# BatMeas5_2_JST.net
KiCad netlist of a schematic drawn in EAGLE
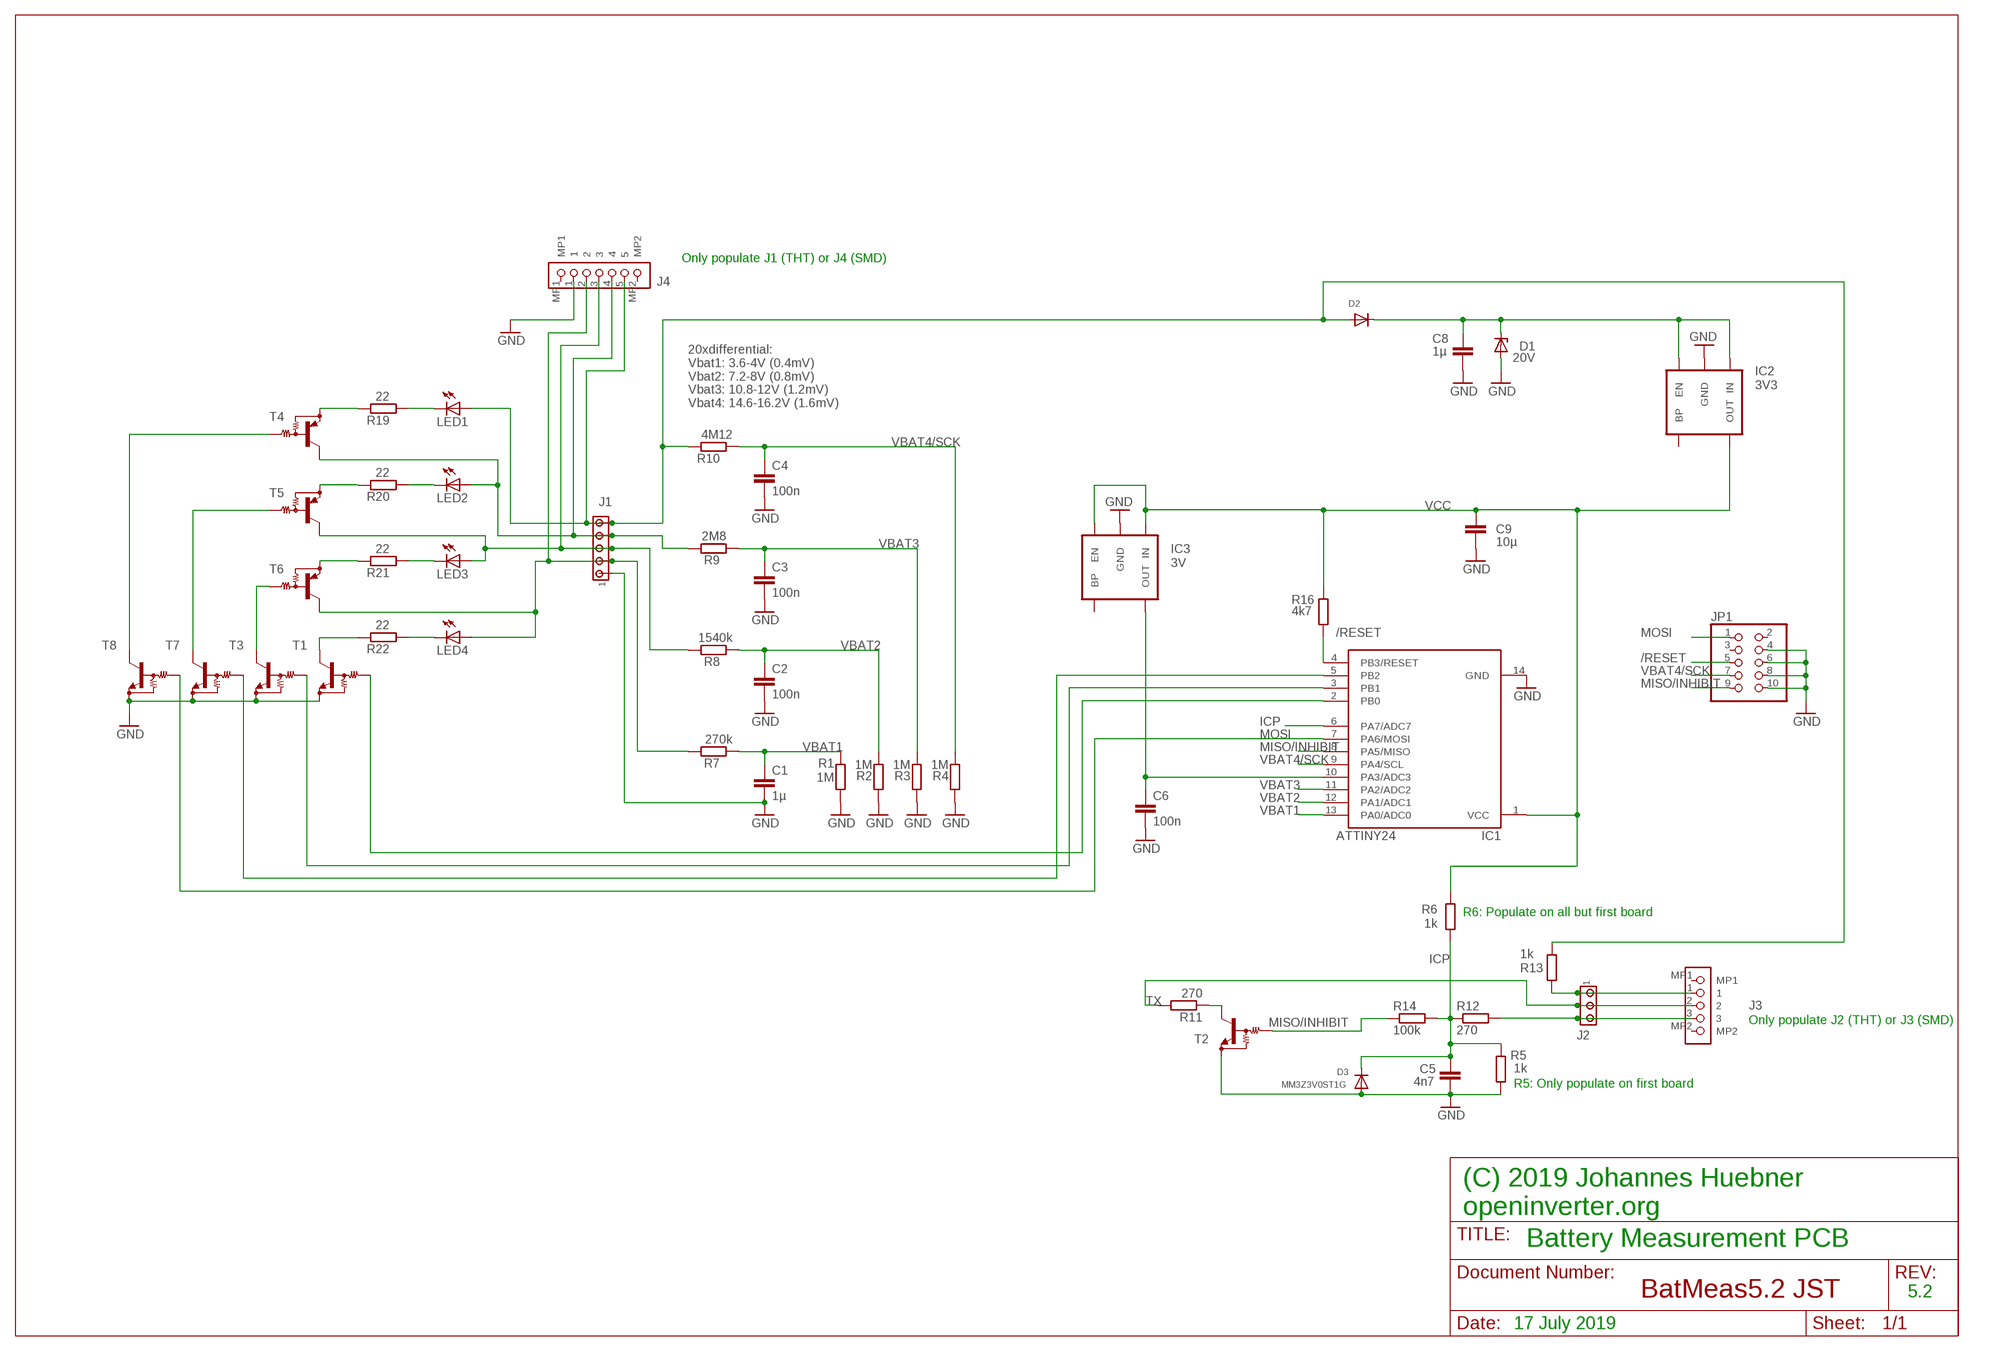
[diagram p0: schematic, sheet 1]

(export (version "E")
  (design (tool "Eeschema 10.0.6"))
  (components
    (comp (ref "C1")
      (value "1µ")
      (footprint "eagle-import:C0603")
      (libsource (lib "eagle-import") (part "C-EUC0603"))
    )
    (comp (ref "C2")
      (value "100n")
      (footprint "eagle-import:C0603")
      (libsource (lib "eagle-import") (part "C-EUC0603"))
    )
    (comp (ref "C3")
      (value "100n")
      (footprint "eagle-import:C0603")
      (libsource (lib "eagle-import") (part "C-EUC0603"))
    )
    (comp (ref "C4")
      (value "100n")
      (footprint "eagle-import:C0603")
      (libsource (lib "eagle-import") (part "C-EUC0603"))
    )
    (comp (ref "C5")
      (value "4n7")
      (footprint "eagle-import:C0603")
      (libsource (lib "eagle-import") (part "C-EUC0603"))
    )
    (comp (ref "C6")
      (value "100n")
      (footprint "eagle-import:C0603")
      (libsource (lib "eagle-import") (part "C-EUC0603"))
    )
    (comp (ref "C8")
      (value "1µ")
      (footprint "eagle-import:C0805")
      (libsource (lib "eagle-import") (part "C-EUC0805"))
    )
    (comp (ref "C9")
      (value "10µ")
      (footprint "eagle-import:C0805")
      (libsource (lib "eagle-import") (part "C-EUC0805"))
    )
    (comp (ref "D1")
      (value "20V")
      (footprint "eagle-import:SMB")
      (libsource (lib "eagle-import") (part "ZENER-DIODESMB"))
    )
    (comp (ref "D2")
      (value "DIODESOD-323F")
      (footprint "eagle-import:SOD-323F")
      (libsource (lib "eagle-import") (part "DIODESOD-323F"))
    )
    (comp (ref "D3")
      (value "MM3Z3V0ST1G")
      (footprint "eagle-import:SOD-323F")
      (libsource (lib "eagle-import") (part "DIODESOD-323F"))
    )
    (comp (ref "IC1")
      (value "ATTINY24")
      (footprint "eagle-import:SO014")
      (libsource (lib "eagle-import") (part "ATTINY24"))
    )
    (comp (ref "IC2")
      (value "3V3")
      (footprint "eagle-import:SOT23-5")
      (libsource (lib "eagle-import") (part "V_REG_LDOSMD"))
    )
    (comp (ref "IC3")
      (value "3V")
      (footprint "eagle-import:SOT23-5")
      (libsource (lib "eagle-import") (part "V_REG_LDOSMD"))
    )
    (comp (ref "J1")
      (value "MTA05-100")
      (footprint "eagle-import:10X05MTA")
      (libsource (lib "eagle-import") (part "MTA05-100"))
    )
    (comp (ref "J2")
      (value "MTA03-100")
      (footprint "eagle-import:10X03MTA")
      (libsource (lib "eagle-import") (part "MTA03-100"))
    )
    (comp (ref "J3")
      (value "BM03B-PASS-1-TFT_(LF)(SN)")
      (footprint "eagle-import:BM03BPASS1TFTLFSN")
      (fields (field (name "MANUFACTURER_PART_NUMBER") "BM03B-PASS-1-TFT (LF)(SN)"))
      (libsource (lib "eagle-import") (part "BM03B-PASS-1-TFT_(LF)(SN)"))
    )
    (comp (ref "J4")
      (value "BM05B-PASS-1-TFT_(LF)(SN)SMD")
      (footprint "eagle-import:BM05BPASS1TFTLFSN")
      (libsource (lib "eagle-import") (part "BM05B-PASS-1-TFT_(LF)(SN)SMD"))
    )
    (comp (ref "JP1")
      (value "PINHD-2X5")
      (footprint "eagle-import:2X05")
      (libsource (lib "eagle-import") (part "PINHD-2X5"))
    )
    (comp (ref "LED1")
      (value "150060GS75000")
      (footprint "eagle-import:CHIPLED_0805")
      (libsource (lib "eagle-import") (part "LEDCHIPLED_0805"))
    )
    (comp (ref "LED2")
      (value "150060GS75000")
      (footprint "eagle-import:CHIPLED_0805")
      (libsource (lib "eagle-import") (part "LEDCHIPLED_0805"))
    )
    (comp (ref "LED3")
      (value "150060GS75000")
      (footprint "eagle-import:CHIPLED_0805")
      (libsource (lib "eagle-import") (part "LEDCHIPLED_0805"))
    )
    (comp (ref "LED4")
      (value "150060GS75000")
      (footprint "eagle-import:CHIPLED_0805")
      (libsource (lib "eagle-import") (part "LEDCHIPLED_0805"))
    )
    (comp (ref "R1")
      (value "1M")
      (footprint "eagle-import:R0603")
      (libsource (lib "eagle-import") (part "R-EU_R0603"))
    )
    (comp (ref "R2")
      (value "1M")
      (footprint "eagle-import:R0603")
      (libsource (lib "eagle-import") (part "R-EU_R0603"))
    )
    (comp (ref "R3")
      (value "1M")
      (footprint "eagle-import:R0603")
      (libsource (lib "eagle-import") (part "R-EU_R0603"))
    )
    (comp (ref "R4")
      (value "1M")
      (footprint "eagle-import:R0603")
      (libsource (lib "eagle-import") (part "R-EU_R0603"))
    )
    (comp (ref "R5")
      (value "1k")
      (footprint "eagle-import:R0603")
      (libsource (lib "eagle-import") (part "R-EU_R0603"))
    )
    (comp (ref "R6")
      (value "1k")
      (footprint "eagle-import:R0603")
      (libsource (lib "eagle-import") (part "R-EU_R0603"))
    )
    (comp (ref "R7")
      (value "270k")
      (footprint "eagle-import:R0603")
      (libsource (lib "eagle-import") (part "R-EU_R0603"))
    )
    (comp (ref "R8")
      (value "1540k")
      (footprint "eagle-import:R0603")
      (libsource (lib "eagle-import") (part "R-EU_R0603"))
    )
    (comp (ref "R9")
      (value "2M8")
      (footprint "eagle-import:R0603")
      (libsource (lib "eagle-import") (part "R-EU_R0603"))
    )
    (comp (ref "R10")
      (value "4M12")
      (footprint "eagle-import:R0603")
      (libsource (lib "eagle-import") (part "R-EU_R0603"))
    )
    (comp (ref "R11")
      (value "270")
      (footprint "eagle-import:R0603")
      (libsource (lib "eagle-import") (part "R-EU_R0603"))
    )
    (comp (ref "R12")
      (value "270")
      (footprint "eagle-import:R0603")
      (libsource (lib "eagle-import") (part "R-EU_R0603"))
    )
    (comp (ref "R13")
      (value "1k")
      (footprint "eagle-import:R0603")
      (libsource (lib "eagle-import") (part "R-EU_R0603"))
    )
    (comp (ref "R14")
      (value "100k")
      (footprint "eagle-import:R0603")
      (libsource (lib "eagle-import") (part "R-EU_R0603"))
    )
    (comp (ref "R16")
      (value "4k7")
      (footprint "eagle-import:R0603")
      (libsource (lib "eagle-import") (part "R-EU_R0603"))
    )
    (comp (ref "R19")
      (value "22")
      (footprint "eagle-import:R0805")
      (libsource (lib "eagle-import") (part "R-EU_R0805"))
    )
    (comp (ref "R20")
      (value "22")
      (footprint "eagle-import:R0805")
      (libsource (lib "eagle-import") (part "R-EU_R0805"))
    )
    (comp (ref "R21")
      (value "22")
      (footprint "eagle-import:R0805")
      (libsource (lib "eagle-import") (part "R-EU_R0805"))
    )
    (comp (ref "R22")
      (value "22")
      (footprint "eagle-import:R0805")
      (libsource (lib "eagle-import") (part "R-EU_R0805"))
    )
    (comp (ref "T1")
      (value "MMUN2233")
      (footprint "eagle-import:SC59-BEC")
      (libsource (lib "eagle-import") (part "-NPN_DRIVER-SC59-BECMUN2211T1"))
    )
    (comp (ref "T2")
      (value "MMUN2233")
      (footprint "eagle-import:SC59-BEC")
      (libsource (lib "eagle-import") (part "-NPN_DRIVER-SC59-BECMUN2211T1"))
    )
    (comp (ref "T3")
      (value "MMUN2233")
      (footprint "eagle-import:SC59-BEC")
      (libsource (lib "eagle-import") (part "-NPN_DRIVER-SC59-BECMUN2211T1"))
    )
    (comp (ref "T4")
      (value "MMUN2111LT1G")
      (footprint "eagle-import:SC59-BEC")
      (libsource (lib "eagle-import") (part "-PNP_DRIVER-SC59-BECMUN2111T1"))
    )
    (comp (ref "T5")
      (value "MMUN2111LT1G")
      (footprint "eagle-import:SC59-BEC")
      (libsource (lib "eagle-import") (part "-PNP_DRIVER-SC59-BECMUN2111T1"))
    )
    (comp (ref "T6")
      (value "MMUN2111LT1G")
      (footprint "eagle-import:SC59-BEC")
      (libsource (lib "eagle-import") (part "-PNP_DRIVER-SC59-BECMUN2111T1"))
    )
    (comp (ref "T7")
      (value "MMUN2233")
      (footprint "eagle-import:SC59-BEC")
      (libsource (lib "eagle-import") (part "-NPN_DRIVER-SC59-BECMUN2211T1"))
    )
    (comp (ref "T8")
      (value "MMUN2233")
      (footprint "eagle-import:SC59-BEC")
      (libsource (lib "eagle-import") (part "-NPN_DRIVER-SC59-BECMUN2211T1"))
    )
  )
  (nets
    (net (code "1") (name "/ICP") (class "Default")
      (node (ref "C5") (pin "1") (pinfunction "1_1") (pintype "passive"))
      (node (ref "D3") (pin "C") (pinfunction "C_C") (pintype "passive"))
      (node (ref "IC1") (pin "6") (pinfunction "PA7/ADC7_6") (pintype "bidirectional"))
      (node (ref "R12") (pin "1") (pinfunction "1_1") (pintype "passive"))
      (node (ref "R14") (pin "2") (pinfunction "2_2") (pintype "passive"))
      (node (ref "R5") (pin "2") (pinfunction "2_2") (pintype "passive"))
      (node (ref "R6") (pin "1") (pinfunction "1_1") (pintype "passive"))
    )
    (net (code "2") (name "/MISO{slash}INHIBIT") (class "Default")
      (node (ref "IC1") (pin "8") (pinfunction "PA5/MISO_8") (pintype "bidirectional"))
      (node (ref "JP1") (pin "9") (pinfunction "9_9") (pintype "passive"))
      (node (ref "R14") (pin "1") (pinfunction "1_1") (pintype "passive"))
      (node (ref "T2") (pin "B") (pinfunction "B_B") (pintype "passive"))
    )
    (net (code "3") (name "/MOSI") (class "Default")
      (node (ref "IC1") (pin "7") (pinfunction "PA6/MOSI_7") (pintype "bidirectional"))
      (node (ref "JP1") (pin "1") (pinfunction "1_1") (pintype "passive"))
      (node (ref "T8") (pin "B") (pinfunction "B_B") (pintype "passive"))
    )
    (net (code "4") (name "/TX") (class "Default")
      (node (ref "J2") (pin "2") (pinfunction "2_2") (pintype "passive"))
      (node (ref "J3") (pin "2") (pinfunction "2_2") (pintype "bidirectional"))
      (node (ref "R11") (pin "2") (pinfunction "2_2") (pintype "passive"))
    )
    (net (code "5") (name "/VBAT1") (class "Default")
      (node (ref "C1") (pin "1") (pinfunction "1_1") (pintype "passive"))
      (node (ref "IC1") (pin "13") (pinfunction "PA0/ADC0_13") (pintype "bidirectional"))
      (node (ref "R1") (pin "1") (pinfunction "1_1") (pintype "passive"))
      (node (ref "R7") (pin "1") (pinfunction "1_1") (pintype "passive"))
    )
    (net (code "6") (name "/VBAT2") (class "Default")
      (node (ref "C2") (pin "1") (pinfunction "1_1") (pintype "passive"))
      (node (ref "IC1") (pin "12") (pinfunction "PA1/ADC1_12") (pintype "bidirectional"))
      (node (ref "R2") (pin "1") (pinfunction "1_1") (pintype "passive"))
      (node (ref "R8") (pin "1") (pinfunction "1_1") (pintype "passive"))
    )
    (net (code "7") (name "/VBAT3") (class "Default")
      (node (ref "C3") (pin "1") (pinfunction "1_1") (pintype "passive"))
      (node (ref "IC1") (pin "11") (pinfunction "PA2/ADC2_11") (pintype "bidirectional"))
      (node (ref "R3") (pin "1") (pinfunction "1_1") (pintype "passive"))
      (node (ref "R9") (pin "1") (pinfunction "1_1") (pintype "passive"))
    )
    (net (code "8") (name "/VBAT4{slash}SCK") (class "Default")
      (node (ref "C4") (pin "1") (pinfunction "1_1") (pintype "passive"))
      (node (ref "IC1") (pin "9") (pinfunction "PA4/SCL_9") (pintype "bidirectional"))
      (node (ref "JP1") (pin "7") (pinfunction "7_7") (pintype "passive"))
      (node (ref "R10") (pin "1") (pinfunction "1_1") (pintype "passive"))
      (node (ref "R4") (pin "1") (pinfunction "1_1") (pintype "passive"))
    )
    (net (code "9") (name "/VCC") (class "Default")
      (node (ref "C9") (pin "1") (pinfunction "1_1") (pintype "passive"))
      (node (ref "IC1") (pin "1") (pinfunction "VCC_1") (pintype "bidirectional"))
      (node (ref "IC2") (pin "5") (pinfunction "OUT_5") (pintype "passive"))
      (node (ref "IC3") (pin "1") (pinfunction "IN_1") (pintype "input"))
      (node (ref "IC3") (pin "3") (pinfunction "EN_3") (pintype "input"))
      (node (ref "R16") (pin "1") (pinfunction "1_1") (pintype "passive"))
      (node (ref "R6") (pin "2") (pinfunction "2_2") (pintype "passive"))
    )
    (net (code "10") (name "/{slash}RESET") (class "Default")
      (node (ref "IC1") (pin "4") (pinfunction "PB3/RESET_4") (pintype "bidirectional"))
      (node (ref "JP1") (pin "5") (pinfunction "5_5") (pintype "passive"))
      (node (ref "R16") (pin "2") (pinfunction "2_2") (pintype "passive"))
    )
    (net (code "11") (name "GND") (class "Default")
      (node (ref "C1") (pin "2") (pinfunction "2_2") (pintype "passive"))
      (node (ref "C2") (pin "2") (pinfunction "2_2") (pintype "passive"))
      (node (ref "C3") (pin "2") (pinfunction "2_2") (pintype "passive"))
      (node (ref "C4") (pin "2") (pinfunction "2_2") (pintype "passive"))
      (node (ref "C5") (pin "2") (pinfunction "2_2") (pintype "passive"))
      (node (ref "C6") (pin "2") (pinfunction "2_2") (pintype "passive"))
      (node (ref "C8") (pin "2") (pinfunction "2_2") (pintype "passive"))
      (node (ref "C9") (pin "2") (pinfunction "2_2") (pintype "passive"))
      (node (ref "D1") (pin "A") (pinfunction "A_A") (pintype "passive"))
      (node (ref "D3") (pin "A") (pinfunction "A_A") (pintype "passive"))
      (node (ref "IC1") (pin "14") (pinfunction "GND_14") (pintype "bidirectional"))
      (node (ref "IC2") (pin "2") (pinfunction "GND_2") (pintype "input"))
      (node (ref "IC3") (pin "2") (pinfunction "GND_2") (pintype "input"))
      (node (ref "J1") (pin "1") (pinfunction "1_1") (pintype "passive"))
      (node (ref "J4") (pin "1") (pinfunction "1_1") (pintype "bidirectional"))
      (node (ref "JP1") (pin "10") (pinfunction "10_10") (pintype "passive"))
      (node (ref "JP1") (pin "4") (pinfunction "4_4") (pintype "passive"))
      (node (ref "JP1") (pin "6") (pinfunction "6_6") (pintype "passive"))
      (node (ref "JP1") (pin "8") (pinfunction "8_8") (pintype "passive"))
      (node (ref "R1") (pin "2") (pinfunction "2_2") (pintype "passive"))
      (node (ref "R2") (pin "2") (pinfunction "2_2") (pintype "passive"))
      (node (ref "R3") (pin "2") (pinfunction "2_2") (pintype "passive"))
      (node (ref "R4") (pin "2") (pinfunction "2_2") (pintype "passive"))
      (node (ref "R5") (pin "1") (pinfunction "1_1") (pintype "passive"))
      (node (ref "T1") (pin "E") (pinfunction "E_E") (pintype "passive"))
      (node (ref "T2") (pin "E") (pinfunction "E_E") (pintype "passive"))
      (node (ref "T3") (pin "E") (pinfunction "E_E") (pintype "passive"))
      (node (ref "T7") (pin "E") (pinfunction "E_E") (pintype "passive"))
      (node (ref "T8") (pin "E") (pinfunction "E_E") (pintype "passive"))
    )
    (net (code "12") (name "Net-(D2-PadA)") (class "Default")
      (node (ref "D2") (pin "A") (pinfunction "A_A") (pintype "passive"))
      (node (ref "J1") (pin "5") (pinfunction "5_5") (pintype "passive"))
      (node (ref "J4") (pin "5") (pinfunction "5_5") (pintype "bidirectional"))
      (node (ref "LED1") (pin "A") (pinfunction "A_A") (pintype "passive"))
      (node (ref "R10") (pin "2") (pinfunction "2_2") (pintype "passive"))
      (node (ref "R13") (pin "1") (pinfunction "1_1") (pintype "passive"))
    )
    (net (code "13") (name "Net-(IC1-PA3{slash}ADC3)") (class "Default")
      (node (ref "C6") (pin "1") (pinfunction "1_1") (pintype "passive"))
      (node (ref "IC1") (pin "10") (pinfunction "PA3/ADC3_10") (pintype "bidirectional"))
      (node (ref "IC3") (pin "5") (pinfunction "OUT_5") (pintype "passive"))
    )
    (net (code "14") (name "Net-(IC1-PB0)") (class "Default")
      (node (ref "IC1") (pin "2") (pinfunction "PB0_2") (pintype "bidirectional"))
      (node (ref "T1") (pin "B") (pinfunction "B_B") (pintype "passive"))
    )
    (net (code "15") (name "Net-(IC1-PB1)") (class "Default")
      (node (ref "IC1") (pin "3") (pinfunction "PB1_3") (pintype "bidirectional"))
      (node (ref "T3") (pin "B") (pinfunction "B_B") (pintype "passive"))
    )
    (net (code "16") (name "Net-(IC1-PB2)") (class "Default")
      (node (ref "IC1") (pin "5") (pinfunction "PB2_5") (pintype "bidirectional"))
      (node (ref "T7") (pin "B") (pinfunction "B_B") (pintype "passive"))
    )
    (net (code "17") (name "Net-(IC2-EN)") (class "Default")
      (node (ref "C8") (pin "1") (pinfunction "1_1") (pintype "passive"))
      (node (ref "D1") (pin "C") (pinfunction "C_C") (pintype "passive"))
      (node (ref "D2") (pin "C") (pinfunction "C_C") (pintype "passive"))
      (node (ref "IC2") (pin "1") (pinfunction "IN_1") (pintype "input"))
      (node (ref "IC2") (pin "3") (pinfunction "EN_3") (pintype "input"))
    )
    (net (code "18") (name "Net-(J1-Pad2)") (class "Default")
      (node (ref "J1") (pin "2") (pinfunction "2_2") (pintype "passive"))
      (node (ref "J4") (pin "2") (pinfunction "2_2") (pintype "bidirectional"))
      (node (ref "LED4") (pin "A") (pinfunction "A_A") (pintype "passive"))
      (node (ref "R7") (pin "2") (pinfunction "2_2") (pintype "passive"))
      (node (ref "T6") (pin "C") (pinfunction "C_C") (pintype "passive"))
    )
    (net (code "19") (name "Net-(J1-Pad3)") (class "Default")
      (node (ref "J1") (pin "3") (pinfunction "3_3") (pintype "passive"))
      (node (ref "J4") (pin "3") (pinfunction "3_3") (pintype "bidirectional"))
      (node (ref "LED3") (pin "A") (pinfunction "A_A") (pintype "passive"))
      (node (ref "R8") (pin "2") (pinfunction "2_2") (pintype "passive"))
      (node (ref "T5") (pin "C") (pinfunction "C_C") (pintype "passive"))
    )
    (net (code "20") (name "Net-(J1-Pad4)") (class "Default")
      (node (ref "J1") (pin "4") (pinfunction "4_4") (pintype "passive"))
      (node (ref "J4") (pin "4") (pinfunction "4_4") (pintype "bidirectional"))
      (node (ref "LED2") (pin "A") (pinfunction "A_A") (pintype "passive"))
      (node (ref "R9") (pin "2") (pinfunction "2_2") (pintype "passive"))
      (node (ref "T4") (pin "C") (pinfunction "C_C") (pintype "passive"))
    )
    (net (code "21") (name "Net-(J2-Pad1)") (class "Default")
      (node (ref "J2") (pin "1") (pinfunction "1_1") (pintype "passive"))
      (node (ref "J3") (pin "1") (pinfunction "1_1") (pintype "bidirectional"))
      (node (ref "R13") (pin "2") (pinfunction "2_2") (pintype "passive"))
    )
    (net (code "22") (name "Net-(J2-Pad3)") (class "Default")
      (node (ref "J2") (pin "3") (pinfunction "3_3") (pintype "passive"))
      (node (ref "J3") (pin "3") (pinfunction "3_3") (pintype "bidirectional"))
      (node (ref "R12") (pin "2") (pinfunction "2_2") (pintype "passive"))
    )
    (net (code "23") (name "Net-(LED1-PadC)") (class "Default")
      (node (ref "LED1") (pin "C") (pinfunction "C_C") (pintype "passive"))
      (node (ref "R19") (pin "1") (pinfunction "1_1") (pintype "passive"))
    )
    (net (code "24") (name "Net-(LED2-PadC)") (class "Default")
      (node (ref "LED2") (pin "C") (pinfunction "C_C") (pintype "passive"))
      (node (ref "R20") (pin "1") (pinfunction "1_1") (pintype "passive"))
    )
    (net (code "25") (name "Net-(LED3-PadC)") (class "Default")
      (node (ref "LED3") (pin "C") (pinfunction "C_C") (pintype "passive"))
      (node (ref "R21") (pin "1") (pinfunction "1_1") (pintype "passive"))
    )
    (net (code "26") (name "Net-(LED4-PadC)") (class "Default")
      (node (ref "LED4") (pin "C") (pinfunction "C_C") (pintype "passive"))
      (node (ref "R22") (pin "1") (pinfunction "1_1") (pintype "passive"))
    )
    (net (code "27") (name "Net-(R11-Pad1)") (class "Default")
      (node (ref "R11") (pin "1") (pinfunction "1_1") (pintype "passive"))
      (node (ref "T2") (pin "C") (pinfunction "C_C") (pintype "passive"))
    )
    (net (code "28") (name "Net-(R19-Pad2)") (class "Default")
      (node (ref "R19") (pin "2") (pinfunction "2_2") (pintype "passive"))
      (node (ref "T4") (pin "E") (pinfunction "E_E") (pintype "passive"))
    )
    (net (code "29") (name "Net-(R20-Pad2)") (class "Default")
      (node (ref "R20") (pin "2") (pinfunction "2_2") (pintype "passive"))
      (node (ref "T5") (pin "E") (pinfunction "E_E") (pintype "passive"))
    )
    (net (code "30") (name "Net-(R21-Pad2)") (class "Default")
      (node (ref "R21") (pin "2") (pinfunction "2_2") (pintype "passive"))
      (node (ref "T6") (pin "E") (pinfunction "E_E") (pintype "passive"))
    )
    (net (code "31") (name "Net-(R22-Pad2)") (class "Default")
      (node (ref "R22") (pin "2") (pinfunction "2_2") (pintype "passive"))
      (node (ref "T1") (pin "C") (pinfunction "C_C") (pintype "passive"))
    )
    (net (code "32") (name "Net-(T3-PadC)") (class "Default")
      (node (ref "T3") (pin "C") (pinfunction "C_C") (pintype "passive"))
      (node (ref "T6") (pin "B") (pinfunction "B_B") (pintype "passive"))
    )
    (net (code "33") (name "Net-(T4-PadB)") (class "Default")
      (node (ref "T4") (pin "B") (pinfunction "B_B") (pintype "passive"))
      (node (ref "T8") (pin "C") (pinfunction "C_C") (pintype "passive"))
    )
    (net (code "34") (name "Net-(T5-PadB)") (class "Default")
      (node (ref "T5") (pin "B") (pinfunction "B_B") (pintype "passive"))
      (node (ref "T7") (pin "C") (pinfunction "C_C") (pintype "passive"))
    )
    (net (code "35") (name "unconnected-(IC2-BP-Pad4)") (class "Default")
      (node (ref "IC2") (pin "4") (pinfunction "BP_4") (pintype "input"))
    )
    (net (code "36") (name "unconnected-(IC3-BP-Pad4)") (class "Default")
      (node (ref "IC3") (pin "4") (pinfunction "BP_4") (pintype "input"))
    )
    (net (code "37") (name "unconnected-(J3-PadMP1)") (class "Default")
      (node (ref "J3") (pin "MP1") (pinfunction "MP1_MP1") (pintype "bidirectional"))
    )
    (net (code "38") (name "unconnected-(J3-PadMP2)") (class "Default")
      (node (ref "J3") (pin "MP2") (pinfunction "MP2_MP2") (pintype "bidirectional"))
    )
    (net (code "39") (name "unconnected-(J4-PadMP1)") (class "Default")
      (node (ref "J4") (pin "MP1") (pinfunction "MP1_MP1") (pintype "bidirectional"))
    )
    (net (code "40") (name "unconnected-(J4-PadMP2)") (class "Default")
      (node (ref "J4") (pin "MP2") (pinfunction "MP2_MP2") (pintype "bidirectional"))
    )
    (net (code "41") (name "unconnected-(JP1-Pad2)") (class "Default")
      (node (ref "JP1") (pin "2") (pinfunction "2_2") (pintype "passive"))
    )
    (net (code "42") (name "unconnected-(JP1-Pad3)") (class "Default")
      (node (ref "JP1") (pin "3") (pinfunction "3_3") (pintype "passive"))
    )
  )
)
